# SCH_SteamShower.net
KiCad netlist of a schematic drawn in Altium Designer
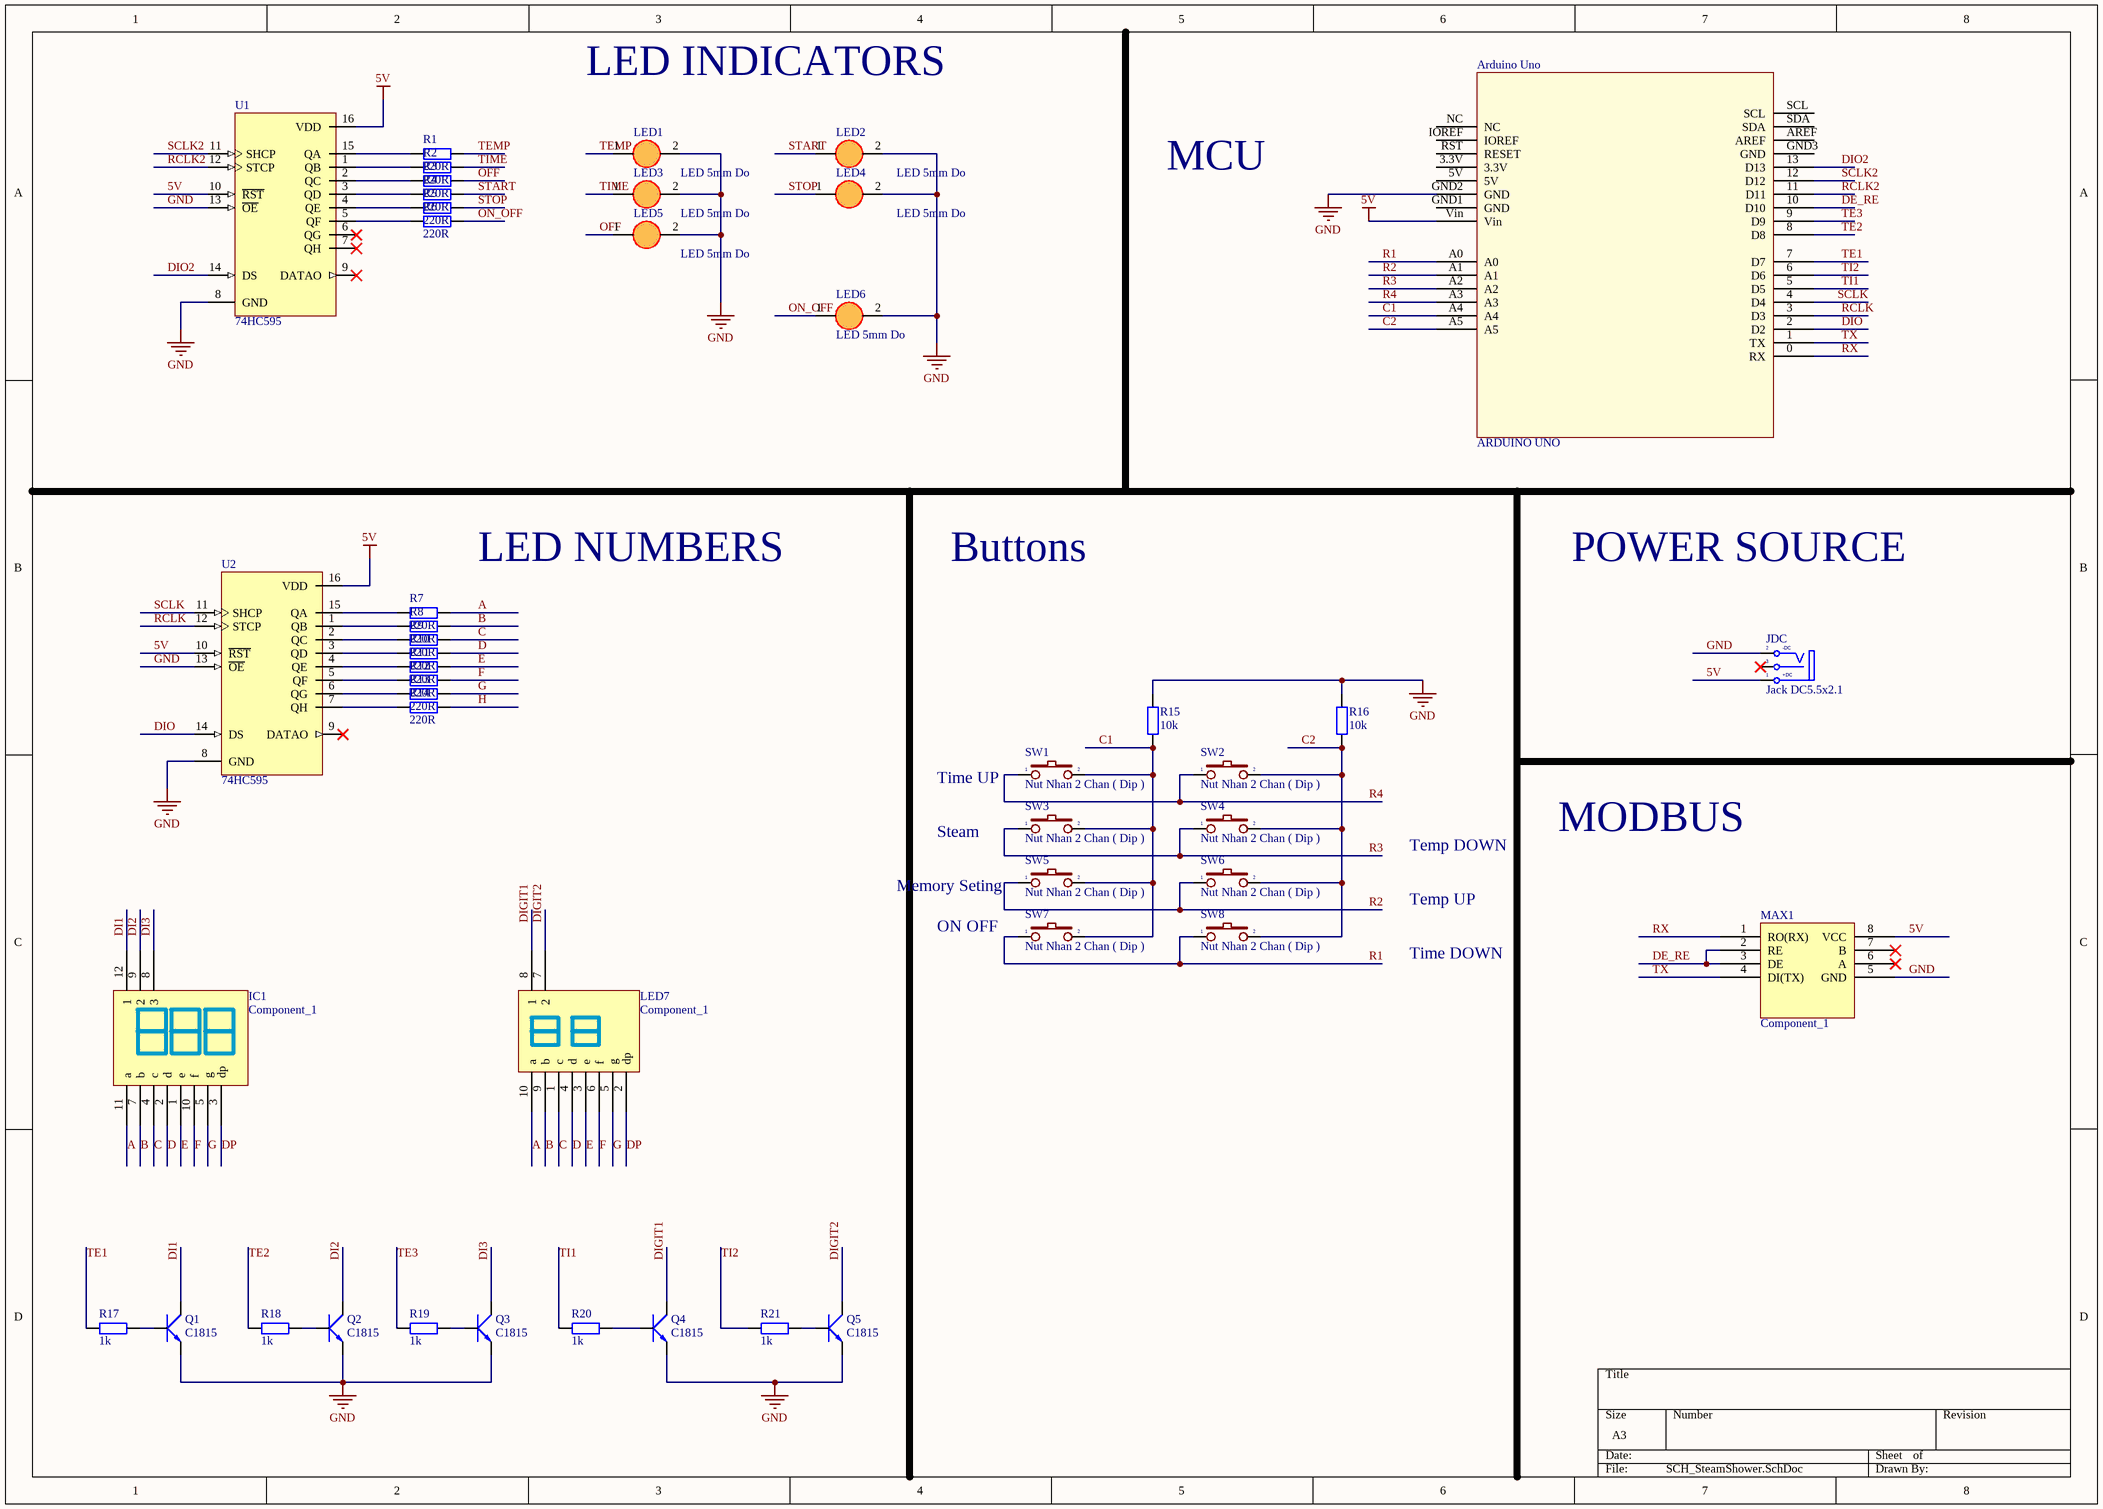
[diagram p0: SCH_SteamShower.SchDoc]

(export (version "E")
  (design (tool "Eeschema 10.0.6"))
  (components
    (comp (ref "Arduino Uno")
      (value "ARDUINO UNO")
      (footprint "ARDUINO UNO")
      (libsource (lib "Arduino") (part "ARDUINO UNO"))
    )
    (comp (ref "IC1")
      (value "Component_1")
      (footprint "7SEG_MPX3")
      (description "5631AS LED 7 Segment 3 digits")
      (libsource (lib "5631AS_Lib") (part "Component_1"))
    )
    (comp (ref "JDC")
      (value "Jack DC5.5x2.1")
      (footprint "DC-IN")
      (description "Cắm")
      (libsource (lib "THU VIEN SCH") (part "Jac_DC"))
    )
    (comp (ref "LED1")
      (value "LED 5mm Do")
      (footprint "LED 5mm DO")
      (description "Cắm")
      (libsource (lib "THU VIEN SCH") (part "LED 5mm Do"))
    )
    (comp (ref "LED2")
      (value "LED 5mm Do")
      (footprint "LED 5mm DO")
      (description "Cắm")
      (libsource (lib "THU VIEN SCH") (part "LED 5mm Do"))
    )
    (comp (ref "LED3")
      (value "LED 5mm Do")
      (footprint "LED 5mm DO")
      (description "Cắm")
      (libsource (lib "THU VIEN SCH") (part "LED 5mm Do"))
    )
    (comp (ref "LED4")
      (value "LED 5mm Do")
      (footprint "LED 5mm DO")
      (description "Cắm")
      (libsource (lib "THU VIEN SCH") (part "LED 5mm Do"))
    )
    (comp (ref "LED5")
      (value "LED 5mm Do")
      (footprint "LED 5mm DO")
      (description "Cắm")
      (libsource (lib "THU VIEN SCH") (part "LED 5mm Do"))
    )
    (comp (ref "LED6")
      (value "LED 5mm Do")
      (footprint "LED 5mm DO")
      (description "Cắm")
      (libsource (lib "THU VIEN SCH") (part "LED 5mm Do"))
    )
    (comp (ref "LED7")
      (value "Component_1")
      (footprint "5621AS_Lib")
      (libsource (lib "5621AS_Lib") (part "Component_1"))
    )
    (comp (ref "MAX1")
      (value "Component_1")
      (footprint "MAX485_Module")
      (libsource (lib "MAX485_Module_Lib") (part "Component_1"))
    )
    (comp (ref "Q1")
      (value "C1815")
      (footprint "QTO-92")
      (description "Dán")
      (libsource (lib "THU VIEN SCH") (part "C1815"))
    )
    (comp (ref "Q2")
      (value "C1815")
      (footprint "QTO-92")
      (description "Dán")
      (libsource (lib "THU VIEN SCH") (part "C1815"))
    )
    (comp (ref "Q3")
      (value "C1815")
      (footprint "QTO-92")
      (description "Dán")
      (libsource (lib "THU VIEN SCH") (part "C1815"))
    )
    (comp (ref "Q4")
      (value "C1815")
      (footprint "QTO-92")
      (description "Dán")
      (libsource (lib "THU VIEN SCH") (part "C1815"))
    )
    (comp (ref "Q5")
      (value "C1815")
      (footprint "QTO-92")
      (description "Dán")
      (libsource (lib "THU VIEN SCH") (part "C1815"))
    )
    (comp (ref "R1")
      (value "220R")
      (footprint "tro vach 1/4w")
      (description "Cắm")
      (libsource (lib "THU VIEN SCH") (part "Tro Vach 1/4W 5% 220R"))
    )
    (comp (ref "R2")
      (value "220R")
      (footprint "tro vach 1/4w")
      (description "Cắm")
      (libsource (lib "THU VIEN SCH") (part "Tro Vach 1/4W 5% 220R"))
    )
    (comp (ref "R3")
      (value "220R")
      (footprint "tro vach 1/4w")
      (description "Cắm")
      (libsource (lib "THU VIEN SCH") (part "Tro Vach 1/4W 5% 220R"))
    )
    (comp (ref "R4")
      (value "220R")
      (footprint "tro vach 1/4w")
      (description "Cắm")
      (libsource (lib "THU VIEN SCH") (part "Tro Vach 1/4W 5% 220R"))
    )
    (comp (ref "R5")
      (value "220R")
      (footprint "tro vach 1/4w")
      (description "Cắm")
      (libsource (lib "THU VIEN SCH") (part "Tro Vach 1/4W 5% 220R"))
    )
    (comp (ref "R6")
      (value "220R")
      (footprint "tro vach 1/4w")
      (description "Cắm")
      (libsource (lib "THU VIEN SCH") (part "Tro Vach 1/4W 5% 220R"))
    )
    (comp (ref "R7")
      (value "220R")
      (footprint "tro vach 1/4w")
      (description "Cắm")
      (libsource (lib "THU VIEN SCH") (part "Tro Vach 1/4W 5% 220R"))
    )
    (comp (ref "R8")
      (value "220R")
      (footprint "tro vach 1/4w")
      (description "Cắm")
      (libsource (lib "THU VIEN SCH") (part "Tro Vach 1/4W 5% 220R"))
    )
    (comp (ref "R9")
      (value "220R")
      (footprint "tro vach 1/4w")
      (description "Cắm")
      (libsource (lib "THU VIEN SCH") (part "Tro Vach 1/4W 5% 220R"))
    )
    (comp (ref "R10")
      (value "220R")
      (footprint "tro vach 1/4w")
      (description "Cắm")
      (libsource (lib "THU VIEN SCH") (part "Tro Vach 1/4W 5% 220R"))
    )
    (comp (ref "R11")
      (value "220R")
      (footprint "tro vach 1/4w")
      (description "Cắm")
      (libsource (lib "THU VIEN SCH") (part "Tro Vach 1/4W 5% 220R"))
    )
    (comp (ref "R12")
      (value "220R")
      (footprint "tro vach 1/4w")
      (description "Cắm")
      (libsource (lib "THU VIEN SCH") (part "Tro Vach 1/4W 5% 220R"))
    )
    (comp (ref "R13")
      (value "220R")
      (footprint "tro vach 1/4w")
      (description "Cắm")
      (libsource (lib "THU VIEN SCH") (part "Tro Vach 1/4W 5% 220R"))
    )
    (comp (ref "R14")
      (value "220R")
      (footprint "tro vach 1/4w")
      (description "Cắm")
      (libsource (lib "THU VIEN SCH") (part "Tro Vach 1/4W 5% 220R"))
    )
    (comp (ref "R15")
      (value "10k")
      (footprint "tro vach 1/4w")
      (description "Căm")
      (libsource (lib "THU VIEN SCH") (part "Tro Vach 1/4W 5% 10k"))
    )
    (comp (ref "R16")
      (value "10k")
      (footprint "tro vach 1/4w")
      (description "Căm")
      (libsource (lib "THU VIEN SCH") (part "Tro Vach 1/4W 5% 10k"))
    )
    (comp (ref "R17")
      (value "1k")
      (footprint "tro vach 1/4w")
      (description "Cắm")
      (libsource (lib "THU VIEN SCH") (part "Tro Vach 1/4W 5% 1k"))
    )
    (comp (ref "R18")
      (value "1k")
      (footprint "tro vach 1/4w")
      (description "Cắm")
      (libsource (lib "THU VIEN SCH") (part "Tro Vach 1/4W 5% 1k"))
    )
    (comp (ref "R19")
      (value "1k")
      (footprint "tro vach 1/4w")
      (description "Cắm")
      (libsource (lib "THU VIEN SCH") (part "Tro Vach 1/4W 5% 1k"))
    )
    (comp (ref "R20")
      (value "1k")
      (footprint "tro vach 1/4w")
      (description "Cắm")
      (libsource (lib "THU VIEN SCH") (part "Tro Vach 1/4W 5% 1k"))
    )
    (comp (ref "R21")
      (value "1k")
      (footprint "tro vach 1/4w")
      (description "Cắm")
      (libsource (lib "THU VIEN SCH") (part "Tro Vach 1/4W 5% 1k"))
    )
    (comp (ref "SW1")
      (value "Nut Nhan 2 Chan ( Dip )")
      (footprint "SW2")
      (description "Cắm")
      (libsource (lib "THU VIEN SCH") (part "Nut Nhan 2 Chan ( Dip )"))
    )
    (comp (ref "SW2")
      (value "Nut Nhan 2 Chan ( Dip )")
      (footprint "SW2")
      (description "Cắm")
      (libsource (lib "THU VIEN SCH") (part "Nut Nhan 2 Chan ( Dip )"))
    )
    (comp (ref "SW3")
      (value "Nut Nhan 2 Chan ( Dip )")
      (footprint "SW2")
      (description "Cắm")
      (libsource (lib "THU VIEN SCH") (part "Nut Nhan 2 Chan ( Dip )"))
    )
    (comp (ref "SW4")
      (value "Nut Nhan 2 Chan ( Dip )")
      (footprint "SW2")
      (description "Cắm")
      (libsource (lib "THU VIEN SCH") (part "Nut Nhan 2 Chan ( Dip )"))
    )
    (comp (ref "SW5")
      (value "Nut Nhan 2 Chan ( Dip )")
      (footprint "SW2")
      (description "Cắm")
      (libsource (lib "THU VIEN SCH") (part "Nut Nhan 2 Chan ( Dip )"))
    )
    (comp (ref "SW6")
      (value "Nut Nhan 2 Chan ( Dip )")
      (footprint "SW2")
      (description "Cắm")
      (libsource (lib "THU VIEN SCH") (part "Nut Nhan 2 Chan ( Dip )"))
    )
    (comp (ref "SW7")
      (value "Nut Nhan 2 Chan ( Dip )")
      (footprint "SW2")
      (description "Cắm")
      (libsource (lib "THU VIEN SCH") (part "Nut Nhan 2 Chan ( Dip )"))
    )
    (comp (ref "SW8")
      (value "Nut Nhan 2 Chan ( Dip )")
      (footprint "SW2")
      (description "Cắm")
      (libsource (lib "THU VIEN SCH") (part "Nut Nhan 2 Chan ( Dip )"))
    )
    (comp (ref "U1")
      (value "74HC595")
      (footprint "DIP16/W0.3")
      (description "Dán")
      (libsource (lib "THU VIEN SCH") (part "74HC595"))
    )
    (comp (ref "U2")
      (value "74HC595")
      (footprint "DIP16/W0.3")
      (description "Dán")
      (libsource (lib "THU VIEN SCH") (part "74HC595"))
    )
  )
  (nets
    (net (code "1") (name "/A") (class "Default")
      (node (ref "IC1") (pin "11") (pinfunction "a_11") (pintype "passive"))
      (node (ref "LED7") (pin "10") (pinfunction "a_10") (pintype "passive"))
      (node (ref "R7") (pin "2") (pinfunction "2_2") (pintype "passive"))
    )
    (net (code "2") (name "/B") (class "Default")
      (node (ref "IC1") (pin "7") (pinfunction "b_7") (pintype "passive"))
      (node (ref "LED7") (pin "9") (pinfunction "b_9") (pintype "passive"))
      (node (ref "R8") (pin "2") (pinfunction "2_2") (pintype "passive"))
    )
    (net (code "3") (name "/C") (class "Default")
      (node (ref "IC1") (pin "4") (pinfunction "c_4") (pintype "passive"))
      (node (ref "LED7") (pin "1") (pinfunction "c_1") (pintype "passive"))
      (node (ref "R9") (pin "2") (pinfunction "2_2") (pintype "passive"))
    )
    (net (code "4") (name "/C1") (class "Default")
      (node (ref "Arduino Uno") (pin "A4") (pinfunction "A4_A4") (pintype "passive"))
      (node (ref "R15") (pin "1") (pinfunction "1_1") (pintype "passive"))
      (node (ref "SW1") (pin "2") (pinfunction "2_2") (pintype "passive"))
      (node (ref "SW3") (pin "2") (pinfunction "2_2") (pintype "passive"))
      (node (ref "SW5") (pin "2") (pinfunction "2_2") (pintype "passive"))
      (node (ref "SW7") (pin "2") (pinfunction "2_2") (pintype "passive"))
    )
    (net (code "5") (name "/C2") (class "Default")
      (node (ref "Arduino Uno") (pin "A5") (pinfunction "A5_A5") (pintype "passive"))
      (node (ref "R16") (pin "1") (pinfunction "1_1") (pintype "passive"))
      (node (ref "SW2") (pin "2") (pinfunction "2_2") (pintype "passive"))
      (node (ref "SW4") (pin "2") (pinfunction "2_2") (pintype "passive"))
      (node (ref "SW6") (pin "2") (pinfunction "2_2") (pintype "passive"))
      (node (ref "SW8") (pin "2") (pinfunction "2_2") (pintype "passive"))
    )
    (net (code "6") (name "/D") (class "Default")
      (node (ref "IC1") (pin "2") (pinfunction "d_2") (pintype "passive"))
      (node (ref "LED7") (pin "4") (pinfunction "d_4") (pintype "passive"))
      (node (ref "R10") (pin "2") (pinfunction "2_2") (pintype "passive"))
    )
    (net (code "7") (name "/DE_RE") (class "Default")
      (node (ref "Arduino Uno") (pin "10") (pinfunction "D10_10") (pintype "passive"))
      (node (ref "MAX1") (pin "2") (pinfunction "RE_2") (pintype "passive"))
      (node (ref "MAX1") (pin "3") (pinfunction "DE_3") (pintype "passive"))
    )
    (net (code "8") (name "/DI1") (class "Default")
      (node (ref "IC1") (pin "12") (pinfunction "1_12") (pintype "passive"))
      (node (ref "Q1") (pin "2") (pinfunction "C_2") (pintype "passive"))
    )
    (net (code "9") (name "/DI2") (class "Default")
      (node (ref "IC1") (pin "9") (pinfunction "2_9") (pintype "passive"))
      (node (ref "Q2") (pin "2") (pinfunction "C_2") (pintype "passive"))
    )
    (net (code "10") (name "/DI3") (class "Default")
      (node (ref "IC1") (pin "8") (pinfunction "3_8") (pintype "passive"))
      (node (ref "Q3") (pin "2") (pinfunction "C_2") (pintype "passive"))
    )
    (net (code "11") (name "/DIGIT1") (class "Default")
      (node (ref "LED7") (pin "8") (pinfunction "1_8") (pintype "passive"))
      (node (ref "Q4") (pin "2") (pinfunction "C_2") (pintype "passive"))
    )
    (net (code "12") (name "/DIGIT2") (class "Default")
      (node (ref "LED7") (pin "7") (pinfunction "2_7") (pintype "passive"))
      (node (ref "Q5") (pin "2") (pinfunction "C_2") (pintype "passive"))
    )
    (net (code "13") (name "/DIO") (class "Default")
      (node (ref "Arduino Uno") (pin "2") (pinfunction "D2_2") (pintype "passive"))
      (node (ref "U2") (pin "14") (pinfunction "DS_14") (pintype "input"))
    )
    (net (code "14") (name "/DIO2") (class "Default")
      (node (ref "Arduino Uno") (pin "13") (pinfunction "D13_13") (pintype "passive"))
      (node (ref "U1") (pin "14") (pinfunction "DS_14") (pintype "input"))
    )
    (net (code "15") (name "/DP") (class "Default")
      (node (ref "IC1") (pin "3") (pinfunction "dp_3") (pintype "passive"))
      (node (ref "LED7") (pin "2") (pinfunction "dp_2") (pintype "passive"))
    )
    (net (code "16") (name "/E") (class "Default")
      (node (ref "IC1") (pin "1") (pinfunction "e_1") (pintype "passive"))
      (node (ref "LED7") (pin "3") (pinfunction "e_3") (pintype "passive"))
      (node (ref "R11") (pin "2") (pinfunction "2_2") (pintype "passive"))
    )
    (net (code "17") (name "/F") (class "Default")
      (node (ref "IC1") (pin "10") (pinfunction "f_10") (pintype "passive"))
      (node (ref "LED7") (pin "6") (pinfunction "f_6") (pintype "passive"))
      (node (ref "R12") (pin "2") (pinfunction "2_2") (pintype "passive"))
    )
    (net (code "18") (name "/G") (class "Default")
      (node (ref "IC1") (pin "5") (pinfunction "g_5") (pintype "passive"))
      (node (ref "LED7") (pin "5") (pinfunction "g_5") (pintype "passive"))
      (node (ref "R13") (pin "2") (pinfunction "2_2") (pintype "passive"))
    )
    (net (code "19") (name "/H") (class "Default")
      (node (ref "R14") (pin "2") (pinfunction "2_2") (pintype "passive"))
    )
    (net (code "20") (name "/OFF") (class "Default")
      (node (ref "LED5") (pin "1") (pinfunction "A_1") (pintype "passive"))
      (node (ref "R3") (pin "2") (pinfunction "2_2") (pintype "passive"))
    )
    (net (code "21") (name "/ON_OFF") (class "Default")
      (node (ref "LED6") (pin "1") (pinfunction "A_1") (pintype "passive"))
      (node (ref "R6") (pin "2") (pinfunction "2_2") (pintype "passive"))
    )
    (net (code "22") (name "/R1") (class "Default")
      (node (ref "Arduino Uno") (pin "A0") (pinfunction "A0_A0") (pintype "passive"))
      (node (ref "SW7") (pin "1") (pinfunction "1_1") (pintype "passive"))
      (node (ref "SW8") (pin "1") (pinfunction "1_1") (pintype "passive"))
    )
    (net (code "23") (name "/R2") (class "Default")
      (node (ref "Arduino Uno") (pin "A1") (pinfunction "A1_A1") (pintype "passive"))
      (node (ref "SW5") (pin "1") (pinfunction "1_1") (pintype "passive"))
      (node (ref "SW6") (pin "1") (pinfunction "1_1") (pintype "passive"))
    )
    (net (code "24") (name "/R3") (class "Default")
      (node (ref "Arduino Uno") (pin "A2") (pinfunction "A2_A2") (pintype "passive"))
      (node (ref "SW3") (pin "1") (pinfunction "1_1") (pintype "passive"))
      (node (ref "SW4") (pin "1") (pinfunction "1_1") (pintype "passive"))
    )
    (net (code "25") (name "/R4") (class "Default")
      (node (ref "Arduino Uno") (pin "A3") (pinfunction "A3_A3") (pintype "passive"))
      (node (ref "SW1") (pin "1") (pinfunction "1_1") (pintype "passive"))
      (node (ref "SW2") (pin "1") (pinfunction "1_1") (pintype "passive"))
    )
    (net (code "26") (name "/RCLK") (class "Default")
      (node (ref "Arduino Uno") (pin "3") (pinfunction "D3_3") (pintype "passive"))
      (node (ref "U2") (pin "12") (pinfunction "STCP_12") (pintype "input"))
    )
    (net (code "27") (name "/RCLK2") (class "Default")
      (node (ref "Arduino Uno") (pin "11") (pinfunction "D11_11") (pintype "passive"))
      (node (ref "U1") (pin "12") (pinfunction "STCP_12") (pintype "input"))
    )
    (net (code "28") (name "/RX") (class "Default")
      (node (ref "Arduino Uno") (pin "0") (pinfunction "RX_0") (pintype "passive"))
      (node (ref "MAX1") (pin "1") (pinfunction "RO(RX)_1") (pintype "passive"))
    )
    (net (code "29") (name "/SCLK") (class "Default")
      (node (ref "Arduino Uno") (pin "4") (pinfunction "D4_4") (pintype "passive"))
      (node (ref "U2") (pin "11") (pinfunction "SHCP_11") (pintype "input"))
    )
    (net (code "30") (name "/SCLK2") (class "Default")
      (node (ref "Arduino Uno") (pin "12") (pinfunction "D12_12") (pintype "passive"))
      (node (ref "U1") (pin "11") (pinfunction "SHCP_11") (pintype "input"))
    )
    (net (code "31") (name "/START") (class "Default")
      (node (ref "LED2") (pin "1") (pinfunction "A_1") (pintype "passive"))
      (node (ref "R4") (pin "2") (pinfunction "2_2") (pintype "passive"))
    )
    (net (code "32") (name "/STOP") (class "Default")
      (node (ref "LED4") (pin "1") (pinfunction "A_1") (pintype "passive"))
      (node (ref "R5") (pin "2") (pinfunction "2_2") (pintype "passive"))
    )
    (net (code "33") (name "/TE1") (class "Default")
      (node (ref "Arduino Uno") (pin "7") (pinfunction "D7_7") (pintype "passive"))
      (node (ref "R17") (pin "1") (pinfunction "1_1") (pintype "passive"))
    )
    (net (code "34") (name "/TE2") (class "Default")
      (node (ref "Arduino Uno") (pin "8") (pinfunction "D8_8") (pintype "passive"))
      (node (ref "R18") (pin "1") (pinfunction "1_1") (pintype "passive"))
    )
    (net (code "35") (name "/TE3") (class "Default")
      (node (ref "Arduino Uno") (pin "9") (pinfunction "D9_9") (pintype "passive"))
      (node (ref "R19") (pin "1") (pinfunction "1_1") (pintype "passive"))
    )
    (net (code "36") (name "/TEMP") (class "Default")
      (node (ref "LED1") (pin "1") (pinfunction "A_1") (pintype "passive"))
      (node (ref "R1") (pin "2") (pinfunction "2_2") (pintype "passive"))
    )
    (net (code "37") (name "/TI1") (class "Default")
      (node (ref "Arduino Uno") (pin "5") (pinfunction "D5_5") (pintype "passive"))
      (node (ref "R20") (pin "1") (pinfunction "1_1") (pintype "passive"))
    )
    (net (code "38") (name "/TI2") (class "Default")
      (node (ref "Arduino Uno") (pin "6") (pinfunction "D6_6") (pintype "passive"))
      (node (ref "R21") (pin "1") (pinfunction "1_1") (pintype "passive"))
    )
    (net (code "39") (name "/TIME") (class "Default")
      (node (ref "LED3") (pin "1") (pinfunction "A_1") (pintype "passive"))
      (node (ref "R2") (pin "2") (pinfunction "2_2") (pintype "passive"))
    )
    (net (code "40") (name "/TX") (class "Default")
      (node (ref "Arduino Uno") (pin "1") (pinfunction "TX_1") (pintype "passive"))
      (node (ref "MAX1") (pin "4") (pinfunction "DI(TX)_4") (pintype "passive"))
    )
    (net (code "41") (name "5V") (class "Default")
      (node (ref "Arduino Uno") (pin "Vin") (pinfunction "Vin_Vin") (pintype "passive"))
      (node (ref "JDC") (pin "1") (pinfunction "T_1") (pintype "passive"))
      (node (ref "MAX1") (pin "8") (pinfunction "VCC_8") (pintype "passive"))
      (node (ref "U1") (pin "10") (pinfunction "~{RST}_10") (pintype "input"))
      (node (ref "U1") (pin "16") (pinfunction "VDD_16") (pintype "power_in"))
      (node (ref "U2") (pin "10") (pinfunction "~{RST}_10") (pintype "input"))
      (node (ref "U2") (pin "16") (pinfunction "VDD_16") (pintype "power_in"))
    )
    (net (code "42") (name "GND") (class "Default")
      (node (ref "Arduino Uno") (pin "GND2") (pinfunction "GND_GND2") (pintype "passive"))
      (node (ref "JDC") (pin "2") (pinfunction "TN_2") (pintype "passive"))
      (node (ref "LED1") (pin "2") (pinfunction "K_2") (pintype "passive"))
      (node (ref "LED2") (pin "2") (pinfunction "K_2") (pintype "passive"))
      (node (ref "LED3") (pin "2") (pinfunction "K_2") (pintype "passive"))
      (node (ref "LED4") (pin "2") (pinfunction "K_2") (pintype "passive"))
      (node (ref "LED5") (pin "2") (pinfunction "K_2") (pintype "passive"))
      (node (ref "LED6") (pin "2") (pinfunction "K_2") (pintype "passive"))
      (node (ref "MAX1") (pin "5") (pinfunction "GND_5") (pintype "passive"))
      (node (ref "Q1") (pin "3") (pinfunction "E_3") (pintype "passive"))
      (node (ref "Q2") (pin "3") (pinfunction "E_3") (pintype "passive"))
      (node (ref "Q3") (pin "3") (pinfunction "E_3") (pintype "passive"))
      (node (ref "Q4") (pin "3") (pinfunction "E_3") (pintype "passive"))
      (node (ref "Q5") (pin "3") (pinfunction "E_3") (pintype "passive"))
      (node (ref "R15") (pin "2") (pinfunction "2_2") (pintype "passive"))
      (node (ref "R16") (pin "2") (pinfunction "2_2") (pintype "passive"))
      (node (ref "U1") (pin "13") (pinfunction "~{OE}_13") (pintype "input"))
      (node (ref "U1") (pin "8") (pinfunction "GND_8") (pintype "power_in"))
      (node (ref "U2") (pin "13") (pinfunction "~{OE}_13") (pintype "input"))
      (node (ref "U2") (pin "8") (pinfunction "GND_8") (pintype "power_in"))
    )
    (net (code "43") (name "Net-(Q1-B)") (class "Default")
      (node (ref "Q1") (pin "1") (pinfunction "B_1") (pintype "passive"))
      (node (ref "R17") (pin "2") (pinfunction "2_2") (pintype "passive"))
    )
    (net (code "44") (name "Net-(Q2-B)") (class "Default")
      (node (ref "Q2") (pin "1") (pinfunction "B_1") (pintype "passive"))
      (node (ref "R18") (pin "2") (pinfunction "2_2") (pintype "passive"))
    )
    (net (code "45") (name "Net-(Q3-B)") (class "Default")
      (node (ref "Q3") (pin "1") (pinfunction "B_1") (pintype "passive"))
      (node (ref "R19") (pin "2") (pinfunction "2_2") (pintype "passive"))
    )
    (net (code "46") (name "Net-(Q4-B)") (class "Default")
      (node (ref "Q4") (pin "1") (pinfunction "B_1") (pintype "passive"))
      (node (ref "R20") (pin "2") (pinfunction "2_2") (pintype "passive"))
    )
    (net (code "47") (name "Net-(Q5-B)") (class "Default")
      (node (ref "Q5") (pin "1") (pinfunction "B_1") (pintype "passive"))
      (node (ref "R21") (pin "2") (pinfunction "2_2") (pintype "passive"))
    )
    (net (code "48") (name "Net-(U1-QA)") (class "Default")
      (node (ref "R1") (pin "1") (pinfunction "1_1") (pintype "passive"))
      (node (ref "U1") (pin "15") (pinfunction "QA_15") (pintype "tri_state"))
    )
    (net (code "49") (name "Net-(U1-QB)") (class "Default")
      (node (ref "R2") (pin "1") (pinfunction "1_1") (pintype "passive"))
      (node (ref "U1") (pin "1") (pinfunction "QB_1") (pintype "tri_state"))
    )
    (net (code "50") (name "Net-(U1-QC)") (class "Default")
      (node (ref "R3") (pin "1") (pinfunction "1_1") (pintype "passive"))
      (node (ref "U1") (pin "2") (pinfunction "QC_2") (pintype "tri_state"))
    )
    (net (code "51") (name "Net-(U1-QD)") (class "Default")
      (node (ref "R4") (pin "1") (pinfunction "1_1") (pintype "passive"))
      (node (ref "U1") (pin "3") (pinfunction "QD_3") (pintype "tri_state"))
    )
    (net (code "52") (name "Net-(U1-QE)") (class "Default")
      (node (ref "R5") (pin "1") (pinfunction "1_1") (pintype "passive"))
      (node (ref "U1") (pin "4") (pinfunction "QE_4") (pintype "tri_state"))
    )
    (net (code "53") (name "Net-(U1-QF)") (class "Default")
      (node (ref "R6") (pin "1") (pinfunction "1_1") (pintype "passive"))
      (node (ref "U1") (pin "5") (pinfunction "QF_5") (pintype "tri_state"))
    )
    (net (code "54") (name "Net-(U2-QA)") (class "Default")
      (node (ref "R7") (pin "1") (pinfunction "1_1") (pintype "passive"))
      (node (ref "U2") (pin "15") (pinfunction "QA_15") (pintype "tri_state"))
    )
    (net (code "55") (name "Net-(U2-QB)") (class "Default")
      (node (ref "R8") (pin "1") (pinfunction "1_1") (pintype "passive"))
      (node (ref "U2") (pin "1") (pinfunction "QB_1") (pintype "tri_state"))
    )
    (net (code "56") (name "Net-(U2-QC)") (class "Default")
      (node (ref "R9") (pin "1") (pinfunction "1_1") (pintype "passive"))
      (node (ref "U2") (pin "2") (pinfunction "QC_2") (pintype "tri_state"))
    )
    (net (code "57") (name "Net-(U2-QD)") (class "Default")
      (node (ref "R10") (pin "1") (pinfunction "1_1") (pintype "passive"))
      (node (ref "U2") (pin "3") (pinfunction "QD_3") (pintype "tri_state"))
    )
    (net (code "58") (name "Net-(U2-QE)") (class "Default")
      (node (ref "R11") (pin "1") (pinfunction "1_1") (pintype "passive"))
      (node (ref "U2") (pin "4") (pinfunction "QE_4") (pintype "tri_state"))
    )
    (net (code "59") (name "Net-(U2-QF)") (class "Default")
      (node (ref "R12") (pin "1") (pinfunction "1_1") (pintype "passive"))
      (node (ref "U2") (pin "5") (pinfunction "QF_5") (pintype "tri_state"))
    )
    (net (code "60") (name "Net-(U2-QG)") (class "Default")
      (node (ref "R13") (pin "1") (pinfunction "1_1") (pintype "passive"))
      (node (ref "U2") (pin "6") (pinfunction "QG_6") (pintype "tri_state"))
    )
    (net (code "61") (name "Net-(U2-QH)") (class "Default")
      (node (ref "R14") (pin "1") (pinfunction "1_1") (pintype "passive"))
      (node (ref "U2") (pin "7") (pinfunction "QH_7") (pintype "tri_state"))
    )
    (net (code "62") (name "unconnected-(Arduino Uno-GND-PadGND1)") (class "Default")
      (node (ref "Arduino Uno") (pin "GND1") (pinfunction "GND_GND1") (pintype "passive"))
    )
    (net (code "63") (name "unconnected-(Arduino Uno-GND-PadGND3)") (class "Default")
      (node (ref "Arduino Uno") (pin "GND3") (pinfunction "GND_GND3") (pintype "passive"))
    )
    (net (code "64") (name "unconnected-(Arduino Uno-Pad3.3V)") (class "Default")
      (node (ref "Arduino Uno") (pin "3.3V") (pinfunction "3.3V_3.3V") (pintype "passive"))
    )
    (net (code "65") (name "unconnected-(Arduino Uno-Pad5V)") (class "Default")
      (node (ref "Arduino Uno") (pin "5V") (pinfunction "5V_5V") (pintype "passive"))
    )
    (net (code "66") (name "unconnected-(Arduino Uno-PadAREF)") (class "Default")
      (node (ref "Arduino Uno") (pin "AREF") (pinfunction "AREF_AREF") (pintype "passive"))
    )
    (net (code "67") (name "unconnected-(Arduino Uno-PadIOREF)") (class "Default")
      (node (ref "Arduino Uno") (pin "IOREF") (pinfunction "IOREF_IOREF") (pintype "passive"))
    )
    (net (code "68") (name "unconnected-(Arduino Uno-PadNC)") (class "Default")
      (node (ref "Arduino Uno") (pin "NC") (pinfunction "NC_NC") (pintype "passive"))
    )
    (net (code "69") (name "unconnected-(Arduino Uno-PadSCL)") (class "Default")
      (node (ref "Arduino Uno") (pin "SCL") (pinfunction "SCL_SCL") (pintype "passive"))
    )
    (net (code "70") (name "unconnected-(Arduino Uno-PadSDA)") (class "Default")
      (node (ref "Arduino Uno") (pin "SDA") (pinfunction "SDA_SDA") (pintype "passive"))
    )
    (net (code "71") (name "unconnected-(Arduino Uno-RESET-PadRST)") (class "Default")
      (node (ref "Arduino Uno") (pin "RST") (pinfunction "RESET_RST") (pintype "passive"))
    )
    (net (code "72") (name "unconnected-(JDC-S-Pad3)") (class "Default")
      (node (ref "JDC") (pin "3") (pinfunction "S_3") (pintype "power_in+no_connect"))
    )
    (net (code "73") (name "unconnected-(MAX1-A-Pad6)") (class "Default")
      (node (ref "MAX1") (pin "6") (pinfunction "A_6") (pintype "passive+no_connect"))
    )
    (net (code "74") (name "unconnected-(MAX1-B-Pad7)") (class "Default")
      (node (ref "MAX1") (pin "7") (pinfunction "B_7") (pintype "passive+no_connect"))
    )
    (net (code "75") (name "unconnected-(U1-DATAO-Pad9)") (class "Default")
      (node (ref "U1") (pin "9") (pinfunction "DATAO_9") (pintype "output+no_connect"))
    )
    (net (code "76") (name "unconnected-(U1-QG-Pad6)") (class "Default")
      (node (ref "U1") (pin "6") (pinfunction "QG_6") (pintype "tri_state+no_connect"))
    )
    (net (code "77") (name "unconnected-(U1-QH-Pad7)") (class "Default")
      (node (ref "U1") (pin "7") (pinfunction "QH_7") (pintype "tri_state+no_connect"))
    )
    (net (code "78") (name "unconnected-(U2-DATAO-Pad9)") (class "Default")
      (node (ref "U2") (pin "9") (pinfunction "DATAO_9") (pintype "output+no_connect"))
    )
  )
)
